# main.net
KiCad netlist of a schematic drawn in EAGLE
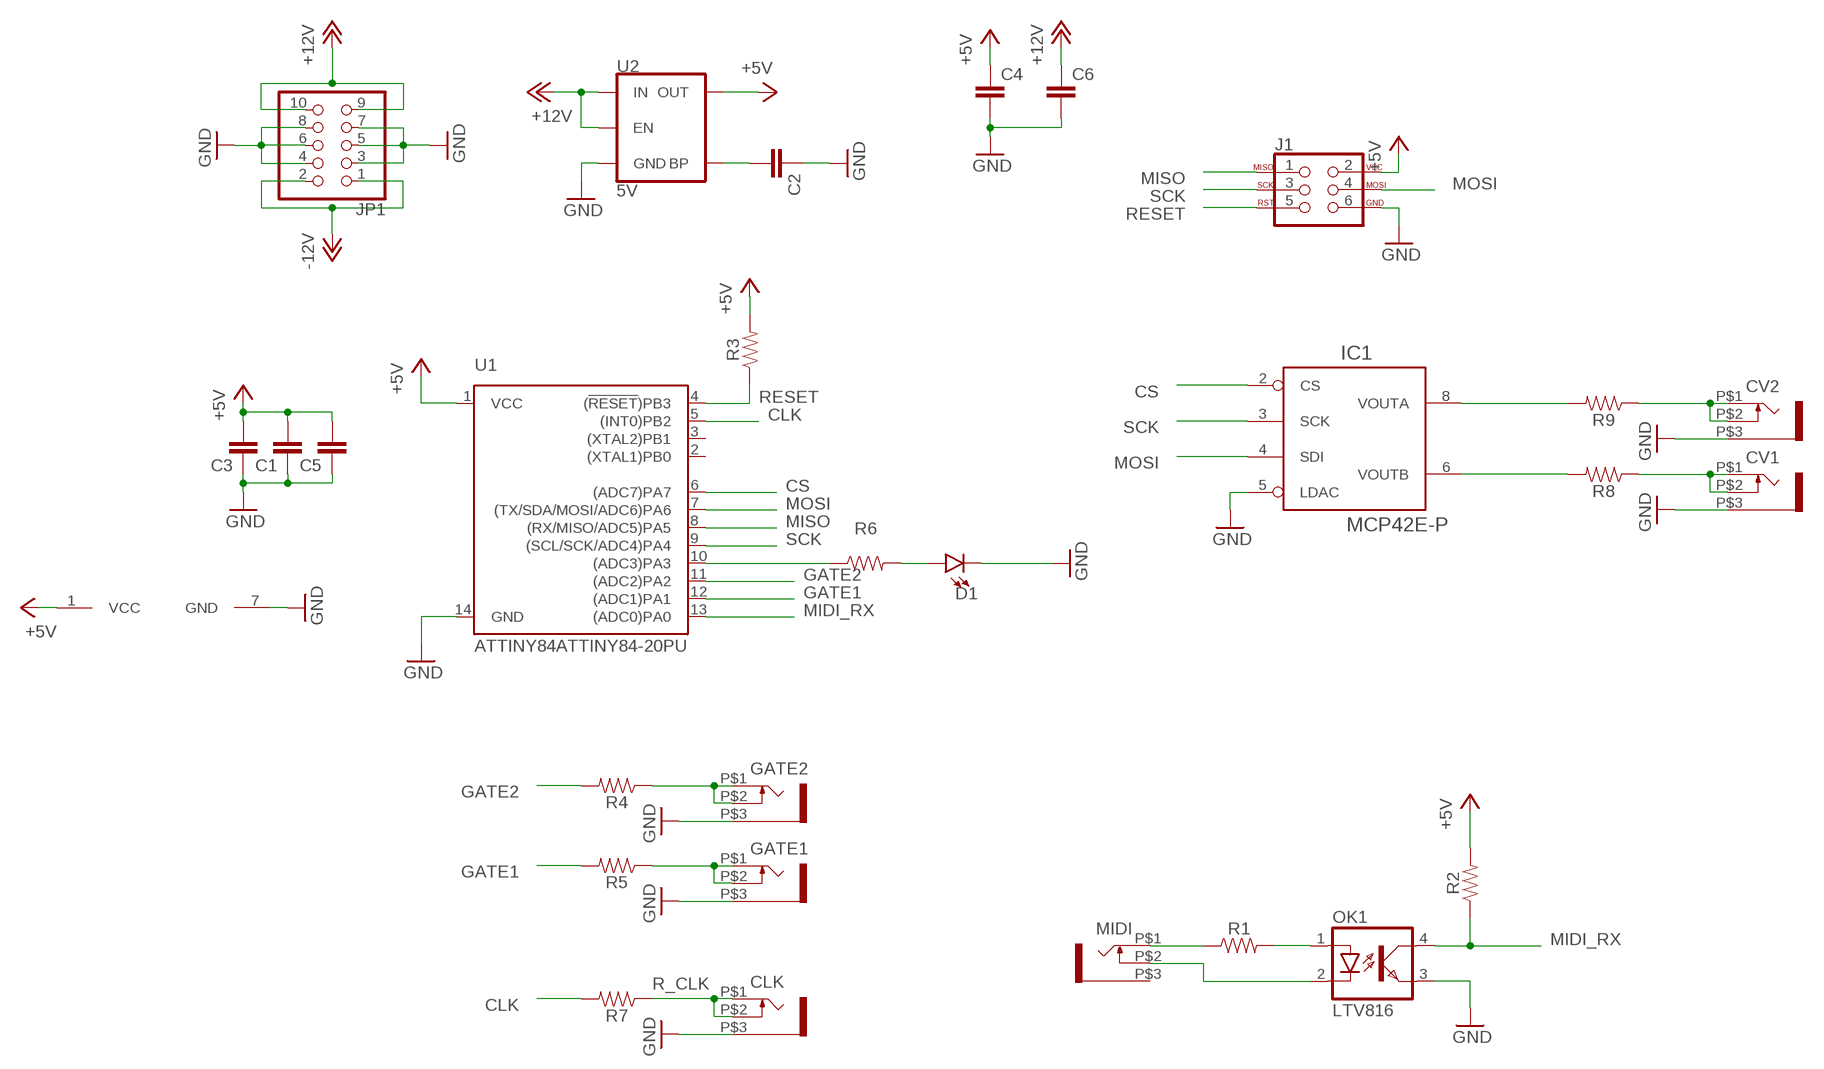
[diagram p0: schematic, sheet 1]

(export (version "E")
  (design (tool "Eeschema 10.0.6"))
  (components
    (comp (ref "C1")
      (value "CAP-0603")
      (footprint "eagle-import:0603")
      (libsource (lib "eagle-import") (part "CAP-0603"))
    )
    (comp (ref "C2")
      (value "CAP-0603")
      (footprint "eagle-import:0603")
      (libsource (lib "eagle-import") (part "CAP-0603"))
    )
    (comp (ref "C3")
      (value "CAP-0603")
      (footprint "eagle-import:0603")
      (libsource (lib "eagle-import") (part "CAP-0603"))
    )
    (comp (ref "C4")
      (value "CAP-0805")
      (footprint "eagle-import:0805")
      (libsource (lib "eagle-import") (part "CAP-0805"))
    )
    (comp (ref "C5")
      (value "CAP-0603")
      (footprint "eagle-import:0603")
      (libsource (lib "eagle-import") (part "CAP-0603"))
    )
    (comp (ref "C6")
      (value "CAP-0805")
      (footprint "eagle-import:0805")
      (libsource (lib "eagle-import") (part "CAP-0805"))
    )
    (comp (ref "CLK")
      (value "WQP-PJ301M-12_JACK")
      (footprint "eagle-import:WQP-PJ301M-12_JACK")
      (libsource (lib "eagle-import") (part "WQP-PJ301M-12_JACK"))
    )
    (comp (ref "CV1")
      (value "WQP-PJ301M-12_JACK")
      (footprint "eagle-import:WQP-PJ301M-12_JACK")
      (libsource (lib "eagle-import") (part "WQP-PJ301M-12_JACK"))
    )
    (comp (ref "CV2")
      (value "WQP-PJ301M-12_JACK")
      (footprint "eagle-import:WQP-PJ301M-12_JACK")
      (libsource (lib "eagle-import") (part "WQP-PJ301M-12_JACK"))
    )
    (comp (ref "D1")
      (value "LED3MM")
      (footprint "eagle-import:LED_3MM")
      (libsource (lib "eagle-import") (part "LED3MM"))
    )
    (comp (ref "GATE1")
      (value "WQP-PJ301M-12_JACK")
      (footprint "eagle-import:WQP-PJ301M-12_JACK")
      (libsource (lib "eagle-import") (part "WQP-PJ301M-12_JACK"))
    )
    (comp (ref "GATE2")
      (value "WQP-PJ301M-12_JACK")
      (footprint "eagle-import:WQP-PJ301M-12_JACK")
      (libsource (lib "eagle-import") (part "WQP-PJ301M-12_JACK"))
    )
    (comp (ref "IC1")
      (value "MCP42E-P")
      (footprint "eagle-import:DIL08")
      (libsource (lib "eagle-import") (part "MCP42E-P"))
    )
    (comp (ref "J1")
      (value "AVR_SPI_PROG_3X2PTH")
      (footprint "eagle-import:2X3")
      (libsource (lib "eagle-import") (part "AVR_SPI_PROG_3X2PTH"))
    )
    (comp (ref "JP1")
      (value "PINHD-2X5")
      (footprint "eagle-import:2X05")
      (libsource (lib "eagle-import") (part "PINHD-2X5"))
    )
    (comp (ref "MIDI")
      (value "WQP-PJ301M-12_JACK")
      (footprint "eagle-import:WQP-PJ301M-12_JACK")
      (libsource (lib "eagle-import") (part "WQP-PJ301M-12_JACK"))
    )
    (comp (ref "OK1")
      (value "LTV816")
      (footprint "eagle-import:DIL04")
      (libsource (lib "eagle-import") (part "LTV816"))
    )
    (comp (ref "R1")
      (value "RESISTORAXIAL-0.3")
      (footprint "eagle-import:AXIAL-0.3")
      (libsource (lib "eagle-import") (part "RESISTORAXIAL-0.3"))
    )
    (comp (ref "R2")
      (value "RESISTORAXIAL-0.3")
      (footprint "eagle-import:AXIAL-0.3")
      (libsource (lib "eagle-import") (part "RESISTORAXIAL-0.3"))
    )
    (comp (ref "R3")
      (value "RESISTOR0603")
      (footprint "eagle-import:0603")
      (libsource (lib "eagle-import") (part "RESISTOR0603"))
    )
    (comp (ref "R4")
      (value "RESISTOR0603")
      (footprint "eagle-import:0603")
      (libsource (lib "eagle-import") (part "RESISTOR0603"))
    )
    (comp (ref "R5")
      (value "RESISTOR0603")
      (footprint "eagle-import:0603")
      (libsource (lib "eagle-import") (part "RESISTOR0603"))
    )
    (comp (ref "R6")
      (value "RESISTOR0603")
      (footprint "eagle-import:0603")
      (libsource (lib "eagle-import") (part "RESISTOR0603"))
    )
    (comp (ref "R7")
      (value "RESISTOR0603")
      (footprint "eagle-import:0603")
      (libsource (lib "eagle-import") (part "RESISTOR0603"))
    )
    (comp (ref "R8")
      (value "RESISTOR0603")
      (footprint "eagle-import:0603")
      (libsource (lib "eagle-import") (part "RESISTOR0603"))
    )
    (comp (ref "R9")
      (value "RESISTOR0603")
      (footprint "eagle-import:0603")
      (libsource (lib "eagle-import") (part "RESISTOR0603"))
    )
    (comp (ref "U1")
      (value "ATTINY84ATTINY84-20PU")
      (footprint "eagle-import:DIP14")
      (libsource (lib "eagle-import") (part "ATTINY84ATTINY84-20PU"))
    )
    (comp (ref "U2")
      (value "5V")
      (footprint "eagle-import:SOT23-5")
      (libsource (lib "eagle-import") (part "V_REG_MIC52055V"))
    )
  )
  (nets
    (net (code "1") (name "+5V") (class "Default")
      (node (ref "C1") (pin "2") (pinfunction "2_2") (pintype "passive"))
      (node (ref "C3") (pin "2") (pinfunction "2_2") (pintype "passive"))
      (node (ref "C4") (pin "1") (pinfunction "1_1") (pintype "passive"))
      (node (ref "C5") (pin "2") (pinfunction "2_2") (pintype "passive"))
      (node (ref "IC1") (pin "1") (pinfunction "VCC_1") (pintype "power_in"))
      (node (ref "J1") (pin "2") (pinfunction "2_2") (pintype "passive"))
      (node (ref "R2") (pin "P$2") (pinfunction "2_P$2") (pintype "passive"))
      (node (ref "R3") (pin "2") (pinfunction "2_2") (pintype "passive"))
      (node (ref "U1") (pin "1") (pinfunction "VCC_1") (pintype "bidirectional"))
      (node (ref "U2") (pin "5") (pinfunction "OUT_5") (pintype "passive"))
    )
    (net (code "2") (name "+12V") (class "Default")
      (node (ref "C6") (pin "1") (pinfunction "1_1") (pintype "passive"))
      (node (ref "JP1") (pin "10") (pinfunction "10_10") (pintype "passive"))
      (node (ref "JP1") (pin "9") (pinfunction "9_9") (pintype "passive"))
      (node (ref "U2") (pin "1") (pinfunction "IN_1") (pintype "input"))
      (node (ref "U2") (pin "3") (pinfunction "EN_3") (pintype "input"))
    )
    (net (code "3") (name "-12V") (class "Default")
      (node (ref "JP1") (pin "1") (pinfunction "1_1") (pintype "passive"))
      (node (ref "JP1") (pin "2") (pinfunction "2_2") (pintype "passive"))
    )
    (net (code "4") (name "/CLK") (class "Default")
      (node (ref "R7") (pin "2") (pinfunction "2_2") (pintype "passive"))
      (node (ref "U1") (pin "5") (pinfunction "(INT0)PB2_5") (pintype "bidirectional"))
    )
    (net (code "5") (name "/CS") (class "Default")
      (node (ref "IC1") (pin "2") (pinfunction "CS_2") (pintype "input"))
      (node (ref "U1") (pin "6") (pinfunction "(ADC7)PA7_6") (pintype "bidirectional"))
    )
    (net (code "6") (name "/GATE1") (class "Default")
      (node (ref "R5") (pin "2") (pinfunction "2_2") (pintype "passive"))
      (node (ref "U1") (pin "12") (pinfunction "(ADC1)PA1_12") (pintype "bidirectional"))
    )
    (net (code "7") (name "/GATE2") (class "Default")
      (node (ref "R4") (pin "2") (pinfunction "2_2") (pintype "passive"))
      (node (ref "U1") (pin "11") (pinfunction "(ADC2)PA2_11") (pintype "bidirectional"))
    )
    (net (code "8") (name "/MIDI_RX") (class "Default")
      (node (ref "OK1") (pin "4") (pinfunction "COL_4") (pintype "passive"))
      (node (ref "R2") (pin "P$1") (pinfunction "1_P$1") (pintype "passive"))
      (node (ref "U1") (pin "13") (pinfunction "(ADC0)PA0_13") (pintype "bidirectional"))
    )
    (net (code "9") (name "/MISO") (class "Default")
      (node (ref "J1") (pin "1") (pinfunction "1_1") (pintype "passive"))
      (node (ref "U1") (pin "8") (pinfunction "(RX/MISO/ADC5)PA5_8") (pintype "bidirectional"))
    )
    (net (code "10") (name "/MOSI") (class "Default")
      (node (ref "IC1") (pin "4") (pinfunction "SDI_4") (pintype "input"))
      (node (ref "J1") (pin "4") (pinfunction "4_4") (pintype "passive"))
      (node (ref "U1") (pin "7") (pinfunction "(TX/SDA/MOSI/ADC6)PA6_7") (pintype "bidirectional"))
    )
    (net (code "11") (name "/RESET") (class "Default")
      (node (ref "J1") (pin "5") (pinfunction "5_5") (pintype "passive"))
      (node (ref "R3") (pin "1") (pinfunction "1_1") (pintype "passive"))
      (node (ref "U1") (pin "4") (pinfunction "(~{RESET})PB3_4") (pintype "bidirectional"))
    )
    (net (code "12") (name "/R_CLK") (class "Default")
      (node (ref "CLK") (pin "P$1") (pinfunction "2_P$1") (pintype "passive"))
      (node (ref "CLK") (pin "P$2") (pinfunction "3_P$2") (pintype "passive"))
      (node (ref "R7") (pin "1") (pinfunction "1_1") (pintype "passive"))
    )
    (net (code "13") (name "/SCK") (class "Default")
      (node (ref "IC1") (pin "3") (pinfunction "SCK_3") (pintype "input"))
      (node (ref "J1") (pin "3") (pinfunction "3_3") (pintype "passive"))
      (node (ref "U1") (pin "9") (pinfunction "(SCL/SCK/ADC4)PA4_9") (pintype "bidirectional"))
    )
    (net (code "14") (name "GND") (class "Default")
      (node (ref "C1") (pin "1") (pinfunction "1_1") (pintype "passive"))
      (node (ref "C2") (pin "1") (pinfunction "1_1") (pintype "passive"))
      (node (ref "C3") (pin "1") (pinfunction "1_1") (pintype "passive"))
      (node (ref "C4") (pin "2") (pinfunction "2_2") (pintype "passive"))
      (node (ref "C5") (pin "1") (pinfunction "1_1") (pintype "passive"))
      (node (ref "C6") (pin "2") (pinfunction "2_2") (pintype "passive"))
      (node (ref "CLK") (pin "P$3") (pinfunction "1_P$3") (pintype "passive"))
      (node (ref "CV1") (pin "P$3") (pinfunction "1_P$3") (pintype "passive"))
      (node (ref "CV2") (pin "P$3") (pinfunction "1_P$3") (pintype "passive"))
      (node (ref "D1") (pin "K") (pinfunction "C_K") (pintype "passive"))
      (node (ref "GATE1") (pin "P$3") (pinfunction "1_P$3") (pintype "passive"))
      (node (ref "GATE2") (pin "P$3") (pinfunction "1_P$3") (pintype "passive"))
      (node (ref "IC1") (pin "5") (pinfunction "LDAC_5") (pintype "input"))
      (node (ref "IC1") (pin "7") (pinfunction "GND_7") (pintype "power_in"))
      (node (ref "J1") (pin "6") (pinfunction "6_6") (pintype "passive"))
      (node (ref "JP1") (pin "3") (pinfunction "3_3") (pintype "passive"))
      (node (ref "JP1") (pin "4") (pinfunction "4_4") (pintype "passive"))
      (node (ref "JP1") (pin "5") (pinfunction "5_5") (pintype "passive"))
      (node (ref "JP1") (pin "6") (pinfunction "6_6") (pintype "passive"))
      (node (ref "JP1") (pin "7") (pinfunction "7_7") (pintype "passive"))
      (node (ref "JP1") (pin "8") (pinfunction "8_8") (pintype "passive"))
      (node (ref "OK1") (pin "3") (pinfunction "EMIT_3") (pintype "passive"))
      (node (ref "U1") (pin "14") (pinfunction "GND_14") (pintype "bidirectional"))
      (node (ref "U2") (pin "2") (pinfunction "GND_2") (pintype "input"))
    )
    (net (code "15") (name "Net-(CV1-2)") (class "Default")
      (node (ref "CV1") (pin "P$1") (pinfunction "2_P$1") (pintype "passive"))
      (node (ref "CV1") (pin "P$2") (pinfunction "3_P$2") (pintype "passive"))
      (node (ref "R8") (pin "1") (pinfunction "1_1") (pintype "passive"))
    )
    (net (code "16") (name "Net-(CV2-2)") (class "Default")
      (node (ref "CV2") (pin "P$1") (pinfunction "2_P$1") (pintype "passive"))
      (node (ref "CV2") (pin "P$2") (pinfunction "3_P$2") (pintype "passive"))
      (node (ref "R9") (pin "1") (pinfunction "1_1") (pintype "passive"))
    )
    (net (code "17") (name "Net-(D1-PadA)") (class "Default")
      (node (ref "D1") (pin "A") (pinfunction "A_A") (pintype "passive"))
      (node (ref "R6") (pin "2") (pinfunction "2_2") (pintype "passive"))
    )
    (net (code "18") (name "Net-(GATE1-2)") (class "Default")
      (node (ref "GATE1") (pin "P$1") (pinfunction "2_P$1") (pintype "passive"))
      (node (ref "GATE1") (pin "P$2") (pinfunction "3_P$2") (pintype "passive"))
      (node (ref "R5") (pin "1") (pinfunction "1_1") (pintype "passive"))
    )
    (net (code "19") (name "Net-(GATE2-2)") (class "Default")
      (node (ref "GATE2") (pin "P$1") (pinfunction "2_P$1") (pintype "passive"))
      (node (ref "GATE2") (pin "P$2") (pinfunction "3_P$2") (pintype "passive"))
      (node (ref "R4") (pin "1") (pinfunction "1_1") (pintype "passive"))
    )
    (net (code "20") (name "Net-(IC1A-VOUTA)") (class "Default")
      (node (ref "IC1") (pin "8") (pinfunction "VOUTA_8") (pintype "output"))
      (node (ref "R9") (pin "2") (pinfunction "2_2") (pintype "passive"))
    )
    (net (code "21") (name "Net-(IC1A-VOUTB)") (class "Default")
      (node (ref "IC1") (pin "6") (pinfunction "VOUTB_6") (pintype "output"))
      (node (ref "R8") (pin "2") (pinfunction "2_2") (pintype "passive"))
    )
    (net (code "22") (name "Net-(MIDI-2)") (class "Default")
      (node (ref "MIDI") (pin "P$1") (pinfunction "2_P$1") (pintype "passive"))
      (node (ref "R1") (pin "P$1") (pinfunction "1_P$1") (pintype "passive"))
    )
    (net (code "23") (name "Net-(MIDI-3)") (class "Default")
      (node (ref "MIDI") (pin "P$2") (pinfunction "3_P$2") (pintype "passive"))
      (node (ref "OK1") (pin "2") (pinfunction "C_2") (pintype "passive"))
    )
    (net (code "24") (name "Net-(OK1-A)") (class "Default")
      (node (ref "OK1") (pin "1") (pinfunction "A_1") (pintype "passive"))
      (node (ref "R1") (pin "P$2") (pinfunction "2_P$2") (pintype "passive"))
    )
    (net (code "25") (name "Net-(U1-(ADC3)PA3)") (class "Default")
      (node (ref "R6") (pin "1") (pinfunction "1_1") (pintype "passive"))
      (node (ref "U1") (pin "10") (pinfunction "(ADC3)PA3_10") (pintype "bidirectional"))
    )
    (net (code "26") (name "Net-(U2-BP)") (class "Default")
      (node (ref "C2") (pin "2") (pinfunction "2_2") (pintype "passive"))
      (node (ref "U2") (pin "4") (pinfunction "BP_4") (pintype "input"))
    )
    (net (code "27") (name "unconnected-(MIDI-1-PadP$3)") (class "Default")
      (node (ref "MIDI") (pin "P$3") (pinfunction "1_P$3") (pintype "passive"))
    )
    (net (code "28") (name "unconnected-(U1-(XTAL1)PB0-Pad2)") (class "Default")
      (node (ref "U1") (pin "2") (pinfunction "(XTAL1)PB0_2") (pintype "bidirectional"))
    )
    (net (code "29") (name "unconnected-(U1-(XTAL2)PB1-Pad3)") (class "Default")
      (node (ref "U1") (pin "3") (pinfunction "(XTAL2)PB1_3") (pintype "bidirectional"))
    )
  )
)
